# RS485.net
KiCad netlist of a schematic drawn in Altium Designer
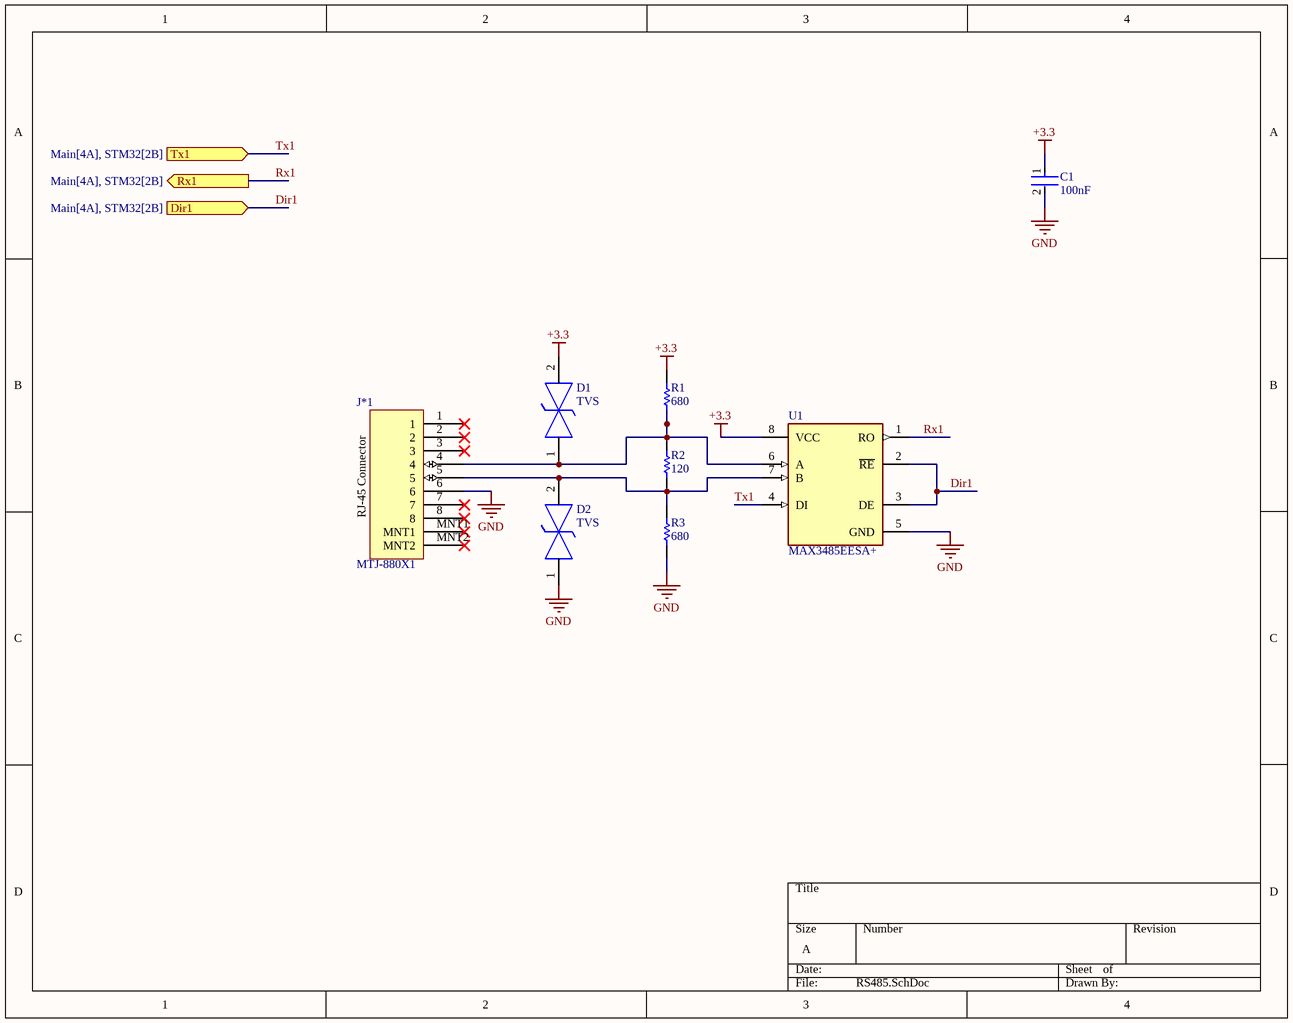
[diagram p0: RS485.SchDoc]

(export (version "E")
  (design (tool "Eeschema 10.0.6"))
  (components
    (comp (ref "C1")
      (value "100nF")
      (footprint "FP-0805-L_2_01_0_2-W_1_25-IPC_B")
      (description "General Purpose Ceramic Capacitor, 0805, 100nF, 10%, X7R, 15%, 100V")
      (fields (field (name "VOLTAGE") "100V") (field (name "TOLERANCE") "10%"))
      (libsource (lib "Altium Content Vault") (part "b4654b650e69147ec39a6b967a45e02"))
    )
    (comp (ref "D1")
      (value "TVS")
      (footprint "FP-SMB-MFG")
      (description "TVS DIODE 28.2V 59V SMB")
      (fields
        (field (name "OCTOPART") "https://octopart.com/sm6t33ca-stmicroelectronics-55399331")
        (field (name "MANUFACTURER PART NUMBER") "SM6T33CA")
      )
      (libsource (lib "Altium Content Vault") (part "ebc102d6f37e12f28676a717a4d7ff6"))
    )
    (comp (ref "D2")
      (value "TVS")
      (footprint "FP-SMB-MFG")
      (description "TVS DIODE 28.2V 59V SMB")
      (fields
        (field (name "OCTOPART") "https://octopart.com/sm6t33ca-stmicroelectronics-55399331")
        (field (name "MANUFACTURER PART NUMBER") "SM6T33CA")
      )
      (libsource (lib "Altium Content Vault") (part "ebc102d6f37e12f28676a717a4d7ff6"))
    )
    (comp (ref "J*1")
      (value "MTJ-880X1")
      (footprint "MTJ-880X1")
      (libsource (lib "Schematic_library") (part "MTJ-880X1"))
    )
    (comp (ref "R1")
      (value "680")
      (footprint "RESC2013X50X30LL20T20")
      (fields (field (name "MANUFACTURER") "Vishay Dale") (field (name "PART NUMBER") "CRCW08050000Z0EA"))
      (libsource (lib "Altium Content Vault") (part "RES"))
    )
    (comp (ref "R2")
      (value "120")
      (footprint "RESC2013X50X30LL20T20")
      (fields (field (name "MANUFACTURER") "Vishay Dale") (field (name "PART NUMBER") "CRCW08050000Z0EA"))
      (libsource (lib "Altium Content Vault") (part "RES"))
    )
    (comp (ref "R3")
      (value "680")
      (footprint "RESC2013X50X30LL20T20")
      (fields (field (name "MANUFACTURER") "Vishay Dale") (field (name "PART NUMBER") "CRCW08050000Z0EA"))
      (libsource (lib "Altium Content Vault") (part "RES"))
    )
    (comp (ref "U1")
      (value "MAX3485EESA+")
      (footprint "FP-S8-5-MFG")
      (description "IC TXRX RS485/422 10MBPS 8SOIC")
      (fields
        (field (name "OCTOPART") "https://octopart.com/max3485eesa%2B-maxim+integrated-39731903")
        (field (name "MANUFACTURER") "Maxim Integrated")
      )
      (libsource (lib "Altium Content Vault") (part "be0caabdb159a9a12bcb36ec340889e"))
    )
  )
  (nets
    (net (code "1") (name "+3.3") (class "Default")
      (node (ref "C1") (pin "1") (pinfunction "1_1") (pintype "passive"))
      (node (ref "D1") (pin "2") (pinfunction "2_2") (pintype "passive"))
      (node (ref "R1") (pin "2") (pinfunction "2_2") (pintype "passive"))
      (node (ref "U1") (pin "8") (pinfunction "VCC_8") (pintype "power_in"))
    )
    (net (code "2") (name "/Dir1") (class "Default")
      (node (ref "U1") (pin "2") (pinfunction "~{RE}_2") (pintype "passive"))
      (node (ref "U1") (pin "3") (pinfunction "DE_3") (pintype "passive"))
    )
    (net (code "3") (name "/Rx1") (class "Default")
      (node (ref "U1") (pin "1") (pinfunction "RO_1") (pintype "output"))
    )
    (net (code "4") (name "/Tx1") (class "Default")
      (node (ref "U1") (pin "4") (pinfunction "DI_4") (pintype "input"))
    )
    (net (code "5") (name "GND") (class "Default")
      (node (ref "C1") (pin "2") (pinfunction "2_2") (pintype "passive"))
      (node (ref "D2") (pin "1") (pinfunction "1_1") (pintype "passive"))
      (node (ref "J*1") (pin "6") (pinfunction "6_6") (pintype "passive"))
      (node (ref "R3") (pin "1") (pinfunction "1_1") (pintype "passive"))
      (node (ref "U1") (pin "5") (pinfunction "GND_5") (pintype "power_in"))
    )
    (net (code "6") (name "Net-(U1-A)") (class "Default")
      (node (ref "D1") (pin "1") (pinfunction "1_1") (pintype "passive"))
      (node (ref "J*1") (pin "4") (pinfunction "4_4") (pintype "bidirectional"))
      (node (ref "R1") (pin "1") (pinfunction "1_1") (pintype "passive"))
      (node (ref "R2") (pin "2") (pinfunction "2_2") (pintype "passive"))
      (node (ref "U1") (pin "6") (pinfunction "A_6") (pintype "input"))
    )
    (net (code "7") (name "Net-(U1-B)") (class "Default")
      (node (ref "D2") (pin "2") (pinfunction "2_2") (pintype "passive"))
      (node (ref "J*1") (pin "5") (pinfunction "5_5") (pintype "bidirectional"))
      (node (ref "R2") (pin "1") (pinfunction "1_1") (pintype "passive"))
      (node (ref "R3") (pin "2") (pinfunction "2_2") (pintype "passive"))
      (node (ref "U1") (pin "7") (pinfunction "B_7") (pintype "input"))
    )
    (net (code "8") (name "unconnected-(J*1-Pad1)") (class "Default")
      (node (ref "J*1") (pin "1") (pinfunction "1_1") (pintype "passive+no_connect"))
    )
    (net (code "9") (name "unconnected-(J*1-Pad2)") (class "Default")
      (node (ref "J*1") (pin "2") (pinfunction "2_2") (pintype "passive+no_connect"))
    )
    (net (code "10") (name "unconnected-(J*1-Pad3)") (class "Default")
      (node (ref "J*1") (pin "3") (pinfunction "3_3") (pintype "passive+no_connect"))
    )
    (net (code "11") (name "unconnected-(J*1-Pad7)") (class "Default")
      (node (ref "J*1") (pin "7") (pinfunction "7_7") (pintype "passive+no_connect"))
    )
    (net (code "12") (name "unconnected-(J*1-Pad8)") (class "Default")
      (node (ref "J*1") (pin "8") (pinfunction "8_8") (pintype "passive+no_connect"))
    )
    (net (code "13") (name "unconnected-(J*1-PadMNT1)") (class "Default")
      (node (ref "J*1") (pin "MNT1") (pinfunction "MNT1_MNT1") (pintype "passive+no_connect"))
    )
    (net (code "14") (name "unconnected-(J*1-PadMNT2)") (class "Default")
      (node (ref "J*1") (pin "MNT2") (pinfunction "MNT2_MNT2") (pintype "passive+no_connect"))
    )
  )
)
